# E-book_Reader_2.net
KiCad netlist of a schematic drawn in EAGLE
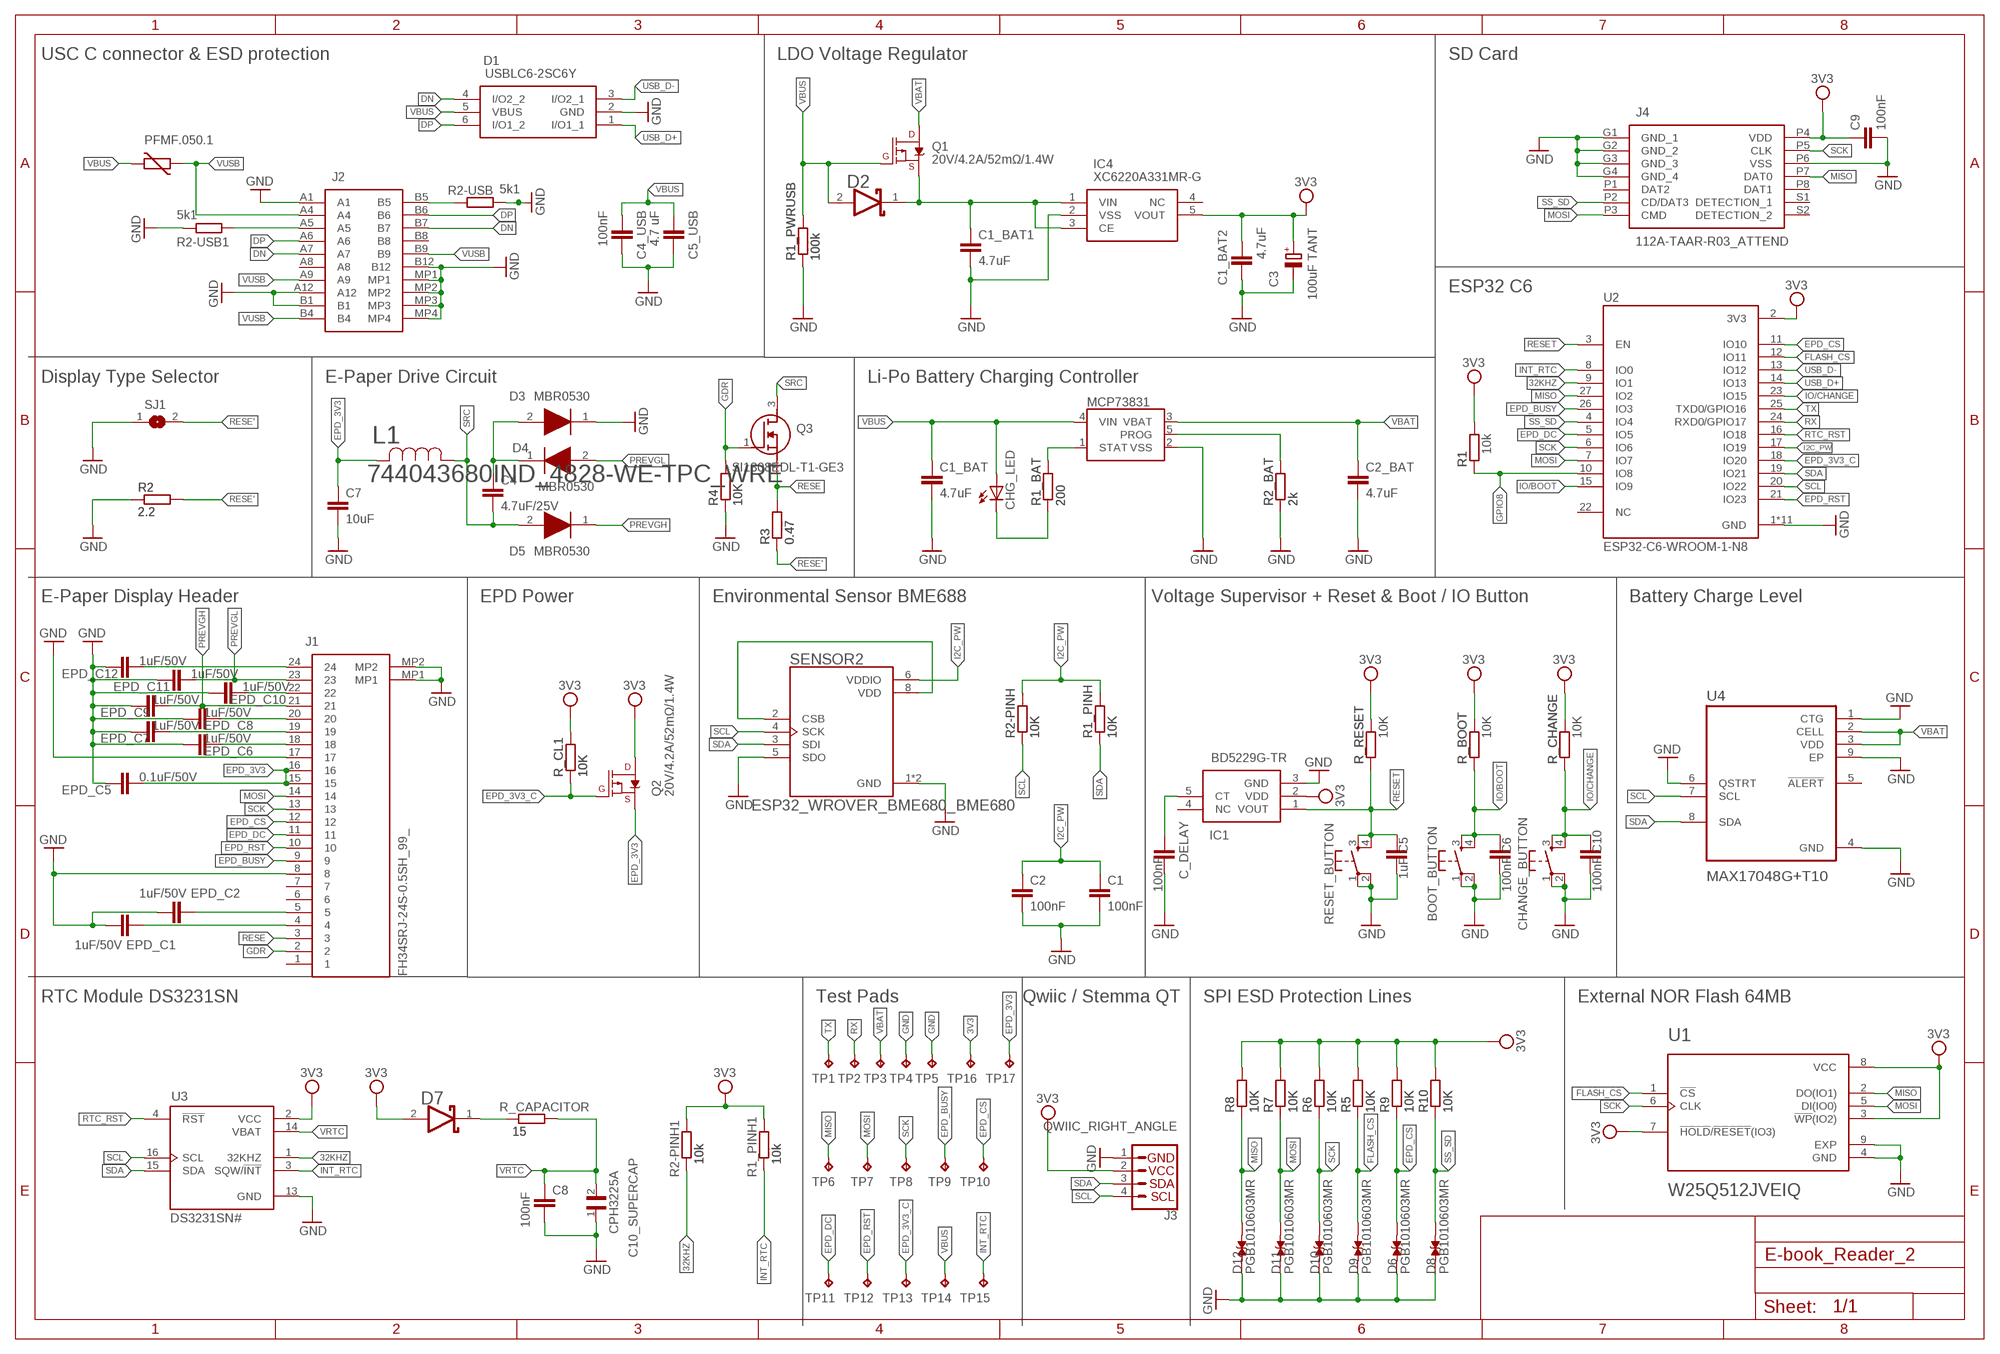
[diagram p0: schematic, sheet 1]

(export (version "E")
  (design (tool "Eeschema 10.0.6"))
  (components
    (comp (ref "BOOT_BUTTON")
      (value "BUTTON_CUSYOMV1")
      (footprint "eagle-import:MYBUTTON")
      (libsource (lib "eagle-import") (part "BUTTON_CUSYOMV1"))
    )
    (comp (ref "C1")
      (value "100nF")
      (footprint "eagle-import:EAGLE-LTSPICE_C0402")
      (libsource (lib "eagle-import") (part "EAGLE-LTSPICE_CC0402"))
    )
    (comp (ref "C1_BAT")
      (value "4.7uF")
      (footprint "eagle-import:EAGLE-LTSPICE_C0402")
      (libsource (lib "eagle-import") (part "EAGLE-LTSPICE_CC0402"))
    )
    (comp (ref "C1_BAT1")
      (value "4.7uF")
      (footprint "eagle-import:EAGLE-LTSPICE_C0402")
      (libsource (lib "eagle-import") (part "EAGLE-LTSPICE_CC0402"))
    )
    (comp (ref "C1_BAT2")
      (value "4.7uF")
      (footprint "eagle-import:EAGLE-LTSPICE_C0402")
      (libsource (lib "eagle-import") (part "EAGLE-LTSPICE_CC0402"))
    )
    (comp (ref "C2")
      (value "100nF")
      (footprint "eagle-import:EAGLE-LTSPICE_C0402")
      (libsource (lib "eagle-import") (part "EAGLE-LTSPICE_CC0402"))
    )
    (comp (ref "C2_BAT")
      (value "4.7uF")
      (footprint "eagle-import:EAGLE-LTSPICE_C0402")
      (libsource (lib "eagle-import") (part "EAGLE-LTSPICE_CC0402"))
    )
    (comp (ref "C3")
      (value "100uF TANT")
      (footprint "eagle-import:RCL_CT3528")
      (libsource (lib "eagle-import") (part "RCL_CPOL-EUCT3528"))
    )
    (comp (ref "C4")
      (value "4.7uF/25V")
      (footprint "eagle-import:EAGLE-LTSPICE_C0402")
      (libsource (lib "eagle-import") (part "EAGLE-LTSPICE_CC0402"))
    )
    (comp (ref "C4_USB")
      (value "100nF")
      (footprint "eagle-import:EAGLE-LTSPICE_C0402")
      (libsource (lib "eagle-import") (part "EAGLE-LTSPICE_CC0402"))
    )
    (comp (ref "C5")
      (value "1uF")
      (footprint "eagle-import:EAGLE-LTSPICE_C0402")
      (libsource (lib "eagle-import") (part "EAGLE-LTSPICE_CC0402"))
    )
    (comp (ref "C5_USB")
      (value "4.7 uF")
      (footprint "eagle-import:EAGLE-LTSPICE_C0402")
      (libsource (lib "eagle-import") (part "EAGLE-LTSPICE_CC0402"))
    )
    (comp (ref "C6")
      (value "100nF")
      (footprint "eagle-import:EAGLE-LTSPICE_C0402")
      (libsource (lib "eagle-import") (part "EAGLE-LTSPICE_CC0402"))
    )
    (comp (ref "C7")
      (value "10uF")
      (footprint "eagle-import:EAGLE-LTSPICE_C0402")
      (libsource (lib "eagle-import") (part "EAGLE-LTSPICE_CC0402"))
    )
    (comp (ref "C8")
      (value "100nF")
      (footprint "eagle-import:EAGLE-LTSPICE_C0402")
      (libsource (lib "eagle-import") (part "EAGLE-LTSPICE_CC0402"))
    )
    (comp (ref "C9")
      (value "100nF")
      (footprint "eagle-import:EAGLE-LTSPICE_C0402")
      (libsource (lib "eagle-import") (part "EAGLE-LTSPICE_CC0402"))
    )
    (comp (ref "C10")
      (value "100nF")
      (footprint "eagle-import:EAGLE-LTSPICE_C0402")
      (libsource (lib "eagle-import") (part "EAGLE-LTSPICE_CC0402"))
    )
    (comp (ref "C10_SUPERCAP")
      (value "CPH3225A")
      (footprint "eagle-import:CAPCP3225X100N")
      (fields (field (name "MF") "Seiko Instruments"))
      (libsource (lib "eagle-import") (part "CPH3225A"))
    )
    (comp (ref "CHANGE_BUTTON")
      (value "BUTTON_CUSYOMV1")
      (footprint "eagle-import:MYBUTTON")
      (libsource (lib "eagle-import") (part "BUTTON_CUSYOMV1"))
    )
    (comp (ref "CHG_LED")
      (value "ADAFRUIT_LEDCHIP-LED0603")
      (footprint "eagle-import:ADAFRUIT_CHIP-LED0603")
      (libsource (lib "eagle-import") (part "ADAFRUIT_LEDCHIP-LED0603"))
    )
    (comp (ref "C_DELAY")
      (value "100nF")
      (footprint "eagle-import:EAGLE-LTSPICE_C0402")
      (libsource (lib "eagle-import") (part "EAGLE-LTSPICE_CC0402"))
    )
    (comp (ref "D1")
      (value "USBLC6-2SC6Y")
      (footprint "eagle-import:SOT95P280X145-6N")
      (fields (field (name "MF") "STMicroelectronics"))
      (libsource (lib "eagle-import") (part "USBLC6-2SC6Y"))
    )
    (comp (ref "D2")
      (value "ESP32_WROVER_AVX---SD0805S020S1R0_AVX_SD0805S020S1R0_0_0AVX_SD0805S020S1R0_0_0")
      (footprint "eagle-import:ESP32_WROVER_AVX---SD0805S020S1R0_AVX_SD0805S020S1R0_0")
      (fields
        (field (name "DIGIKEY_PART_NUMBER") "478-7800-1-ND")
        (field (name "MF") "AVX")
        (field (name "MOUSER_PART_NUMBER") "581-SD0805S020S1R0")
      )
      (libsource (lib "eagle-import") (part "ESP32_WROVER_AVX---SD0805S020S1R0_AVX_SD0805S020S1R0_0_0AVX_SD0805S020S1R0_0_0"))
    )
    (comp (ref "D3")
      (value "MBR0530")
      (footprint "eagle-import:SOD3716X135N")
      (fields (field (name "MF") "ON Semiconductor"))
      (libsource (lib "eagle-import") (part "MBR0530"))
    )
    (comp (ref "D4")
      (value "MBR0530")
      (footprint "eagle-import:SOD3716X135N")
      (fields (field (name "MF") "ON Semiconductor"))
      (libsource (lib "eagle-import") (part "MBR0530"))
    )
    (comp (ref "D5")
      (value "MBR0530")
      (footprint "eagle-import:SOD3716X135N")
      (fields (field (name "MF") "ON Semiconductor"))
      (libsource (lib "eagle-import") (part "MBR0530"))
    )
    (comp (ref "D6")
      (value "PGB1010603MR")
      (footprint "eagle-import:DIOC1608X36N")
      (fields (field (name "MF") "Littelfuse Inc."))
      (libsource (lib "eagle-import") (part "PGB1010603MR"))
    )
    (comp (ref "D7")
      (value "ESP32_WROVER_AVX---SD0805S020S1R0_AVX_SD0805S020S1R0_0_0AVX_SD0805S020S1R0_0_0")
      (footprint "eagle-import:ESP32_WROVER_AVX---SD0805S020S1R0_AVX_SD0805S020S1R0_0")
      (fields
        (field (name "DIGIKEY_PART_NUMBER") "478-7800-1-ND")
        (field (name "MF") "AVX")
        (field (name "MOUSER_PART_NUMBER") "581-SD0805S020S1R0")
      )
      (libsource (lib "eagle-import") (part "ESP32_WROVER_AVX---SD0805S020S1R0_AVX_SD0805S020S1R0_0_0AVX_SD0805S020S1R0_0_0"))
    )
    (comp (ref "D8")
      (value "PGB1010603MR")
      (footprint "eagle-import:DIOC1608X36N")
      (fields (field (name "MF") "Littelfuse Inc."))
      (libsource (lib "eagle-import") (part "PGB1010603MR"))
    )
    (comp (ref "D9")
      (value "PGB1010603MR")
      (footprint "eagle-import:DIOC1608X36N")
      (fields (field (name "MF") "Littelfuse Inc."))
      (libsource (lib "eagle-import") (part "PGB1010603MR"))
    )
    (comp (ref "D10")
      (value "PGB1010603MR")
      (footprint "eagle-import:DIOC1608X36N")
      (fields (field (name "MF") "Littelfuse Inc."))
      (libsource (lib "eagle-import") (part "PGB1010603MR"))
    )
    (comp (ref "D11")
      (value "PGB1010603MR")
      (footprint "eagle-import:DIOC1608X36N")
      (fields (field (name "MF") "Littelfuse Inc."))
      (libsource (lib "eagle-import") (part "PGB1010603MR"))
    )
    (comp (ref "D12")
      (value "PGB1010603MR")
      (footprint "eagle-import:DIOC1608X36N")
      (fields (field (name "MF") "Littelfuse Inc."))
      (libsource (lib "eagle-import") (part "PGB1010603MR"))
    )
    (comp (ref "EPD_C1")
      (value "1uF/50V")
      (footprint "eagle-import:EAGLE-LTSPICE_C0402")
      (libsource (lib "eagle-import") (part "EAGLE-LTSPICE_CC0402"))
    )
    (comp (ref "EPD_C2")
      (value "1uF/50V")
      (footprint "eagle-import:EAGLE-LTSPICE_C0402")
      (libsource (lib "eagle-import") (part "EAGLE-LTSPICE_CC0402"))
    )
    (comp (ref "EPD_C5")
      (value "0.1uF/50V")
      (footprint "eagle-import:EAGLE-LTSPICE_C0402")
      (libsource (lib "eagle-import") (part "EAGLE-LTSPICE_CC0402"))
    )
    (comp (ref "EPD_C6")
      (value "1uF/50V")
      (footprint "eagle-import:EAGLE-LTSPICE_C0402")
      (libsource (lib "eagle-import") (part "EAGLE-LTSPICE_CC0402"))
    )
    (comp (ref "EPD_C7")
      (value "1uF/50V")
      (footprint "eagle-import:EAGLE-LTSPICE_C0402")
      (libsource (lib "eagle-import") (part "EAGLE-LTSPICE_CC0402"))
    )
    (comp (ref "EPD_C8")
      (value "1uF/50V")
      (footprint "eagle-import:EAGLE-LTSPICE_C0402")
      (libsource (lib "eagle-import") (part "EAGLE-LTSPICE_CC0402"))
    )
    (comp (ref "EPD_C9")
      (value "1uF/50V")
      (footprint "eagle-import:EAGLE-LTSPICE_C0402")
      (libsource (lib "eagle-import") (part "EAGLE-LTSPICE_CC0402"))
    )
    (comp (ref "EPD_C10")
      (value "1uF/50V")
      (footprint "eagle-import:EAGLE-LTSPICE_C0402")
      (libsource (lib "eagle-import") (part "EAGLE-LTSPICE_CC0402"))
    )
    (comp (ref "EPD_C11")
      (value "1uF/50V")
      (footprint "eagle-import:EAGLE-LTSPICE_C0402")
      (libsource (lib "eagle-import") (part "EAGLE-LTSPICE_CC0402"))
    )
    (comp (ref "EPD_C12")
      (value "1uF/50V")
      (footprint "eagle-import:EAGLE-LTSPICE_C0402")
      (libsource (lib "eagle-import") (part "EAGLE-LTSPICE_CC0402"))
    )
    (comp (ref "IC1")
      (value "BD5229G-TR")
      (footprint "eagle-import:SOT95P280X125-5N")
      (fields (field (name "MOUSER_PART_NUMBER") "755-BD5229G-TR"))
      (libsource (lib "eagle-import") (part "BD5229G-TR"))
    )
    (comp (ref "IC4")
      (value "XC6220A331MR-G")
      (footprint "eagle-import:SOT95P280X120-5N")
      (fields (field (name "MOUSER_PART_NUMBER") "865-XC6220A331MR-G"))
      (libsource (lib "eagle-import") (part "XC6220A331MR-G"))
    )
    (comp (ref "J1")
      (value "FH34SRJ-24S-0.5SH_99_")
      (footprint "eagle-import:FH34SRJ24S05SH99")
      (fields
        (field (name "MANUFACTURER_PART_NUMBER") "FH34SRJ-24S-0.5SH(99)")
        (field (name "MOUSER_PART_NUMBER") "798-FH34SRJ24S05SH99")
      )
      (libsource (lib "eagle-import") (part "FH34SRJ-24S-0.5SH_99_"))
    )
    (comp (ref "J2")
      (value "SAMACSYS_PARTS_USB4110-GF-A")
      (footprint "eagle-import:SAMACSYS_PARTS_USB4110GFA")
      (fields
        (field (name "MANUFACTURER_PART_NUMBER") "USB4110-GF-A")
        (field (name "MOUSER_PART_NUMBER") "640-USB4110-GF-A")
      )
      (libsource (lib "eagle-import") (part "SAMACSYS_PARTS_USB4110-GF-A"))
    )
    (comp (ref "J3")
      (value "QWIIC_RIGHT_ANGLE")
      (footprint "eagle-import:JST04_1MM_RA")
      (libsource (lib "eagle-import") (part "QWIIC_CONNECTORJS-1MM"))
    )
    (comp (ref "J4")
      (value "112A-TAAR-R03_ATTEND")
      (footprint "eagle-import:112ATAARR03ATTEND")
      (fields (field (name "MANUFACTURER_PART_NUMBER") "112A-TAAR-R03 ATTEND"))
      (libsource (lib "eagle-import") (part "112A-TAAR-R03_ATTEND"))
    )
    (comp (ref "L1")
      (value "744043680IND_4828-WE-TPC_WRE")
      (footprint "eagle-import:IND_4828-WE-TPC_WRE")
      (fields
        (field (name "MANUFACTURER_PART_NUMBER") "744043680")
        (field (name "COPYRIGHT") "Copyright (C) 2024 Ultra Librarian. All rights reserved.")
      )
      (libsource (lib "eagle-import") (part "744043680IND_4828-WE-TPC_WRE"))
    )
    (comp (ref "MCP73831")
      (value "ESP32_WROVER_SPARKFUN-IC-POWER_MCP73831")
      (footprint "eagle-import:ESP32_WROVER_SPARKFUN-IC-POWER_SOT23-5")
      (libsource (lib "eagle-import") (part "ESP32_WROVER_SPARKFUN-IC-POWER_MCP73831"))
    )
    (comp (ref "PFMF.050.1")
      (value "ESP32C6_VARISTORCN1812")
      (footprint "eagle-import:ESP32C6_VARISTOR_CT_CN1812")
      (libsource (lib "eagle-import") (part "ESP32C6_VARISTORCN1812"))
    )
    (comp (ref "Q1")
      (value "20V/4.2A/52mΩ/1.4W")
      (footprint "eagle-import:ESP32_WROVER_SPARKFUN-DISCRETESEMI_SOT23-3")
      (libsource (lib "eagle-import") (part "ESP32_WROVER_SPARKFUN-DISCRETESEMI_MOSFET_PCH-DMG2305UX-7"))
    )
    (comp (ref "Q2")
      (value "20V/4.2A/52mΩ/1.4W")
      (footprint "eagle-import:ESP32_WROVER_SPARKFUN-DISCRETESEMI_SOT23-3")
      (libsource (lib "eagle-import") (part "ESP32_WROVER_SPARKFUN-DISCRETESEMI_MOSFET_PCH-DMG2305UX-7"))
    )
    (comp (ref "Q3")
      (value "SI1308EDL-T1-GE3")
      (footprint "eagle-import:SOT65P210X110-3N")
      (fields (field (name "MF") "Vishay Siliconix"))
      (libsource (lib "eagle-import") (part "SI1308EDL-T1-GE3"))
    )
    (comp (ref "R1")
      (value "10k")
      (footprint "eagle-import:ESP32_WROVER_EAGLE-LTSPICE_R0402")
      (libsource (lib "eagle-import") (part "ESP32_WROVER_EAGLE-LTSPICE_RR0402"))
    )
    (comp (ref "R1_BAT")
      (value "200")
      (footprint "eagle-import:ESP32_WROVER_EAGLE-LTSPICE_R0402")
      (libsource (lib "eagle-import") (part "ESP32_WROVER_EAGLE-LTSPICE_RR0402"))
    )
    (comp (ref "R1_PINH")
      (value "10K")
      (footprint "eagle-import:ESP32_WROVER_EAGLE-LTSPICE_R0402")
      (libsource (lib "eagle-import") (part "ESP32_WROVER_EAGLE-LTSPICE_RR0402"))
    )
    (comp (ref "R1_PINH1")
      (value "10k")
      (footprint "eagle-import:ESP32_WROVER_EAGLE-LTSPICE_R0402")
      (libsource (lib "eagle-import") (part "ESP32_WROVER_EAGLE-LTSPICE_RR0402"))
    )
    (comp (ref "R1_PWRUSB")
      (value "100k")
      (footprint "eagle-import:ESP32_WROVER_EAGLE-LTSPICE_R0402")
      (libsource (lib "eagle-import") (part "ESP32_WROVER_EAGLE-LTSPICE_RR0402"))
    )
    (comp (ref "R2")
      (value "2.2")
      (footprint "eagle-import:ESP32_WROVER_EAGLE-LTSPICE_R0402")
      (libsource (lib "eagle-import") (part "ESP32_WROVER_EAGLE-LTSPICE_RR0402"))
    )
    (comp (ref "R2-PINH")
      (value "10K")
      (footprint "eagle-import:ESP32_WROVER_EAGLE-LTSPICE_R0402")
      (libsource (lib "eagle-import") (part "ESP32_WROVER_EAGLE-LTSPICE_RR0402"))
    )
    (comp (ref "R2-PINH1")
      (value "10k")
      (footprint "eagle-import:ESP32_WROVER_EAGLE-LTSPICE_R0402")
      (libsource (lib "eagle-import") (part "ESP32_WROVER_EAGLE-LTSPICE_RR0402"))
    )
    (comp (ref "R2-USB")
      (value "5k1")
      (footprint "eagle-import:ESP32_WROVER_EAGLE-LTSPICE_R0402")
      (libsource (lib "eagle-import") (part "ESP32_WROVER_EAGLE-LTSPICE_RR0402"))
    )
    (comp (ref "R2-USB1")
      (value "5k1")
      (footprint "eagle-import:ESP32_WROVER_EAGLE-LTSPICE_R0402")
      (libsource (lib "eagle-import") (part "ESP32_WROVER_EAGLE-LTSPICE_RR0402"))
    )
    (comp (ref "R2_BAT")
      (value "2k")
      (footprint "eagle-import:ESP32_WROVER_EAGLE-LTSPICE_R0402")
      (libsource (lib "eagle-import") (part "ESP32_WROVER_EAGLE-LTSPICE_RR0402"))
    )
    (comp (ref "R3")
      (value "0.47")
      (footprint "eagle-import:ESP32_WROVER_EAGLE-LTSPICE_R0402")
      (libsource (lib "eagle-import") (part "ESP32_WROVER_EAGLE-LTSPICE_RR0402"))
    )
    (comp (ref "R4")
      (value "10K")
      (footprint "eagle-import:ESP32_WROVER_EAGLE-LTSPICE_R0402")
      (libsource (lib "eagle-import") (part "ESP32_WROVER_EAGLE-LTSPICE_RR0402"))
    )
    (comp (ref "R5")
      (value "10K")
      (footprint "eagle-import:ESP32_WROVER_EAGLE-LTSPICE_R0402")
      (libsource (lib "eagle-import") (part "ESP32_WROVER_EAGLE-LTSPICE_RR0402"))
    )
    (comp (ref "R6")
      (value "10K")
      (footprint "eagle-import:ESP32_WROVER_EAGLE-LTSPICE_R0402")
      (libsource (lib "eagle-import") (part "ESP32_WROVER_EAGLE-LTSPICE_RR0402"))
    )
    (comp (ref "R7")
      (value "10K")
      (footprint "eagle-import:ESP32_WROVER_EAGLE-LTSPICE_R0402")
      (libsource (lib "eagle-import") (part "ESP32_WROVER_EAGLE-LTSPICE_RR0402"))
    )
    (comp (ref "R8")
      (value "10K")
      (footprint "eagle-import:ESP32_WROVER_EAGLE-LTSPICE_R0402")
      (libsource (lib "eagle-import") (part "ESP32_WROVER_EAGLE-LTSPICE_RR0402"))
    )
    (comp (ref "R9")
      (value "10K")
      (footprint "eagle-import:ESP32_WROVER_EAGLE-LTSPICE_R0402")
      (libsource (lib "eagle-import") (part "ESP32_WROVER_EAGLE-LTSPICE_RR0402"))
    )
    (comp (ref "R10")
      (value "10K")
      (footprint "eagle-import:ESP32_WROVER_EAGLE-LTSPICE_R0402")
      (libsource (lib "eagle-import") (part "ESP32_WROVER_EAGLE-LTSPICE_RR0402"))
    )
    (comp (ref "RESET_BUTTON")
      (value "BUTTON_CUSYOMV1")
      (footprint "eagle-import:MYBUTTON")
      (libsource (lib "eagle-import") (part "BUTTON_CUSYOMV1"))
    )
    (comp (ref "R_BOOT")
      (value "10K")
      (footprint "eagle-import:ESP32_WROVER_EAGLE-LTSPICE_R0402")
      (libsource (lib "eagle-import") (part "ESP32_WROVER_EAGLE-LTSPICE_RR0402"))
    )
    (comp (ref "R_CAPACITOR")
      (value "15")
      (footprint "eagle-import:ESP32_WROVER_EAGLE-LTSPICE_R0402")
      (libsource (lib "eagle-import") (part "ESP32_WROVER_EAGLE-LTSPICE_RR0402"))
    )
    (comp (ref "R_CHANGE")
      (value "10K")
      (footprint "eagle-import:ESP32_WROVER_EAGLE-LTSPICE_R0402")
      (libsource (lib "eagle-import") (part "ESP32_WROVER_EAGLE-LTSPICE_RR0402"))
    )
    (comp (ref "R_CL1")
      (value "10K")
      (footprint "eagle-import:ESP32_WROVER_EAGLE-LTSPICE_R0402")
      (libsource (lib "eagle-import") (part "ESP32_WROVER_EAGLE-LTSPICE_RR0402"))
    )
    (comp (ref "R_RESET")
      (value "10K")
      (footprint "eagle-import:ESP32_WROVER_EAGLE-LTSPICE_R0402")
      (libsource (lib "eagle-import") (part "ESP32_WROVER_EAGLE-LTSPICE_RR0402"))
    )
    (comp (ref "SENSOR2")
      (value "ESP32_WROVER_BME680_BME680")
      (footprint "eagle-import:ESP32_WROVER_BME680_PSON80P300X300X100-8N")
      (fields (field (name "MF") "Bosch Sensortec") (field (name "MP") "BME680"))
      (libsource (lib "eagle-import") (part "ESP32_WROVER_BME680_BME680"))
    )
    (comp (ref "SJ1") (value "SJ") (footprint "eagle-import:SJ") (libsource (lib "eagle-import") (part "SJ")))
    (comp (ref "TP1")
      (value "TPTP20R")
      (footprint "eagle-import:TP20R")
      (libsource (lib "eagle-import") (part "TPTP20R"))
    )
    (comp (ref "TP2")
      (value "TPTP20R")
      (footprint "eagle-import:TP20R")
      (libsource (lib "eagle-import") (part "TPTP20R"))
    )
    (comp (ref "TP3")
      (value "TPTP20R")
      (footprint "eagle-import:TP20R")
      (libsource (lib "eagle-import") (part "TPTP20R"))
    )
    (comp (ref "TP4")
      (value "TPTP20R")
      (footprint "eagle-import:TP20R")
      (libsource (lib "eagle-import") (part "TPTP20R"))
    )
    (comp (ref "TP5")
      (value "TPTP20R")
      (footprint "eagle-import:TP20R")
      (libsource (lib "eagle-import") (part "TPTP20R"))
    )
    (comp (ref "TP6")
      (value "TPTP20R")
      (footprint "eagle-import:TP20R")
      (libsource (lib "eagle-import") (part "TPTP20R"))
    )
    (comp (ref "TP7")
      (value "TPTP20R")
      (footprint "eagle-import:TP20R")
      (libsource (lib "eagle-import") (part "TPTP20R"))
    )
    (comp (ref "TP8")
      (value "TPTP20R")
      (footprint "eagle-import:TP20R")
      (libsource (lib "eagle-import") (part "TPTP20R"))
    )
    (comp (ref "TP9")
      (value "TPTP20R")
      (footprint "eagle-import:TP20R")
      (libsource (lib "eagle-import") (part "TPTP20R"))
    )
    (comp (ref "TP10")
      (value "TPTP20R")
      (footprint "eagle-import:TP20R")
      (libsource (lib "eagle-import") (part "TPTP20R"))
    )
    (comp (ref "TP11")
      (value "TPTP20R")
      (footprint "eagle-import:TP20R")
      (libsource (lib "eagle-import") (part "TPTP20R"))
    )
    (comp (ref "TP12")
      (value "TPTP20R")
      (footprint "eagle-import:TP20R")
      (libsource (lib "eagle-import") (part "TPTP20R"))
    )
    (comp (ref "TP13")
      (value "TPTP20R")
      (footprint "eagle-import:TP20R")
      (libsource (lib "eagle-import") (part "TPTP20R"))
    )
    (comp (ref "TP14")
      (value "TPTP20R")
      (footprint "eagle-import:TP20R")
      (libsource (lib "eagle-import") (part "TPTP20R"))
    )
    (comp (ref "TP15")
      (value "TPTP20R")
      (footprint "eagle-import:TP20R")
      (libsource (lib "eagle-import") (part "TPTP20R"))
    )
    (comp (ref "TP16")
      (value "TPTP20R")
      (footprint "eagle-import:TP20R")
      (libsource (lib "eagle-import") (part "TPTP20R"))
    )
    (comp (ref "TP17")
      (value "TPTP20R")
      (footprint "eagle-import:TP20R")
      (libsource (lib "eagle-import") (part "TPTP20R"))
    )
    (comp (ref "U1")
      (value "W25Q512JVEIQ")
      (footprint "eagle-import:SON127P600X800X80-9N")
      (fields (field (name "MF") "Winbond Electronics"))
      (libsource (lib "eagle-import") (part "W25Q512JVEIQ"))
    )
    (comp (ref "U2")
      (value "ESP32-C6-WROOM-1-N8")
      (footprint "eagle-import:XCVR_ESP32-C6-WROOM-1-N8")
      (fields (field (name "MF") "Espressif Systems"))
      (libsource (lib "eagle-import") (part "ESP32-C6-WROOM-1-N8"))
    )
    (comp (ref "U3")
      (value "DS3231SN#")
      (footprint "eagle-import:SOIC127P1032X265-16N")
      (fields (field (name "MF") "Analog Devices"))
      (libsource (lib "eagle-import") (part "DS3231SN#"))
    )
    (comp (ref "U4")
      (value "MAX17048G+T10")
      (footprint "eagle-import:SON50P200X200X80-9N")
      (fields (field (name "MF") "Analog Devices"))
      (libsource (lib "eagle-import") (part "MAX17048G+T10"))
    )
  )
  (nets
    (net (code "1") (name "3V3") (class "Default")
      (node (ref "C1_BAT2") (pin "1") (pinfunction "1_1") (pintype "passive"))
      (node (ref "C3") (pin "+") (pinfunction "+_+") (pintype "passive"))
      (node (ref "C9") (pin "1") (pinfunction "1_1") (pintype "passive"))
      (node (ref "D7") (pin "2") (pinfunction "ANODE_2") (pintype "bidirectional"))
      (node (ref "IC1") (pin "2") (pinfunction "VDD_2") (pintype "bidirectional"))
      (node (ref "IC4") (pin "5") (pinfunction "VOUT_5") (pintype "bidirectional"))
      (node (ref "J3") (pin "2") (pinfunction "2_2") (pintype "power_in"))
      (node (ref "J4") (pin "P4") (pinfunction "VDD_P4") (pintype "bidirectional"))
      (node (ref "Q2") (pin "3") (pinfunction "D_3") (pintype "bidirectional"))
      (node (ref "R1") (pin "2") (pinfunction "2_2") (pintype "passive"))
      (node (ref "R10") (pin "2") (pinfunction "2_2") (pintype "passive"))
      (node (ref "R1_PINH1") (pin "2") (pinfunction "2_2") (pintype "passive"))
      (node (ref "R2-PINH1") (pin "2") (pinfunction "2_2") (pintype "passive"))
      (node (ref "R5") (pin "2") (pinfunction "2_2") (pintype "passive"))
      (node (ref "R6") (pin "2") (pinfunction "2_2") (pintype "passive"))
      (node (ref "R7") (pin "2") (pinfunction "2_2") (pintype "passive"))
      (node (ref "R8") (pin "2") (pinfunction "2_2") (pintype "passive"))
      (node (ref "R9") (pin "2") (pinfunction "2_2") (pintype "passive"))
      (node (ref "R_BOOT") (pin "2") (pinfunction "2_2") (pintype "passive"))
      (node (ref "R_CHANGE") (pin "2") (pinfunction "2_2") (pintype "passive"))
      (node (ref "R_CL1") (pin "2") (pinfunction "2_2") (pintype "passive"))
      (node (ref "R_RESET") (pin "2") (pinfunction "2_2") (pintype "passive"))
      (node (ref "TP16") (pin "TP") (pinfunction "TP_TP") (pintype "input"))
      (node (ref "U1") (pin "3") (pinfunction "~{WP}(IO2)_3") (pintype "bidirectional"))
      (node (ref "U1") (pin "7") (pinfunction "~{HOLD}/~{RESET}(IO3)_7") (pintype "bidirectional"))
      (node (ref "U1") (pin "8") (pinfunction "VCC_8") (pintype "power_in"))
      (node (ref "U2") (pin "2") (pinfunction "3V3_2") (pintype "power_in"))
      (node (ref "U3") (pin "2") (pinfunction "VCC_2") (pintype "power_in"))
    )
    (net (code "2") (name "32KHZ") (class "Default")
      (node (ref "R2-PINH1") (pin "1") (pinfunction "1_1") (pintype "passive"))
      (node (ref "U2") (pin "9") (pinfunction "IO1_9") (pintype "bidirectional"))
      (node (ref "U3") (pin "1") (pinfunction "32KHZ_1") (pintype "output"))
    )
    (net (code "3") (name "DN") (class "Default")
      (node (ref "D1") (pin "4") (pinfunction "I/O2_2_4") (pintype "bidirectional"))
      (node (ref "J2") (pin "A7") (pinfunction "A7_A7") (pintype "bidirectional"))
      (node (ref "J2") (pin "B7") (pinfunction "B7_B7") (pintype "bidirectional"))
    )
    (net (code "4") (name "DP") (class "Default")
      (node (ref "D1") (pin "6") (pinfunction "I/O1_2_6") (pintype "bidirectional"))
      (node (ref "J2") (pin "A6") (pinfunction "A6_A6") (pintype "bidirectional"))
      (node (ref "J2") (pin "B6") (pinfunction "B6_B6") (pintype "bidirectional"))
    )
    (net (code "5") (name "EPD_3V3") (class "Default")
      (node (ref "C7") (pin "1") (pinfunction "1_1") (pintype "passive"))
      (node (ref "EPD_C5") (pin "1") (pinfunction "1_1") (pintype "passive"))
      (node (ref "J1") (pin "15") (pinfunction "15_15") (pintype "bidirectional"))
      (node (ref "J1") (pin "16") (pinfunction "16_16") (pintype "bidirectional"))
      (node (ref "L1") (pin "2") (pinfunction "2_2") (pintype "passive"))
      (node (ref "Q2") (pin "2") (pinfunction "S_2") (pintype "bidirectional"))
      (node (ref "TP17") (pin "TP") (pinfunction "TP_TP") (pintype "input"))
    )
    (net (code "6") (name "EPD_3V3_C") (class "Default")
      (node (ref "Q2") (pin "1") (pinfunction "G_1") (pintype "bidirectional"))
      (node (ref "R_CL1") (pin "1") (pinfunction "1_1") (pintype "passive"))
      (node (ref "TP13") (pin "TP") (pinfunction "TP_TP") (pintype "input"))
      (node (ref "U2") (pin "18") (pinfunction "IO20_18") (pintype "bidirectional"))
    )
    (net (code "7") (name "EPD_BUSY") (class "Default")
      (node (ref "J1") (pin "9") (pinfunction "9_9") (pintype "bidirectional"))
      (node (ref "TP9") (pin "TP") (pinfunction "TP_TP") (pintype "input"))
      (node (ref "U2") (pin "26") (pinfunction "IO3_26") (pintype "bidirectional"))
    )
    (net (code "8") (name "EPD_CS") (class "Default")
      (node (ref "D6") (pin "2") (pinfunction "2_2") (pintype "passive"))
      (node (ref "J1") (pin "12") (pinfunction "12_12") (pintype "bidirectional"))
      (node (ref "R9") (pin "1") (pinfunction "1_1") (pintype "passive"))
      (node (ref "TP10") (pin "TP") (pinfunction "TP_TP") (pintype "input"))
      (node (ref "U2") (pin "11") (pinfunction "IO10_11") (pintype "bidirectional"))
    )
    (net (code "9") (name "EPD_DC") (class "Default")
      (node (ref "J1") (pin "11") (pinfunction "11_11") (pintype "bidirectional"))
      (node (ref "TP11") (pin "TP") (pinfunction "TP_TP") (pintype "input"))
      (node (ref "U2") (pin "5") (pinfunction "IO5_5") (pintype "bidirectional"))
    )
    (net (code "10") (name "EPD_RST") (class "Default")
      (node (ref "J1") (pin "10") (pinfunction "10_10") (pintype "bidirectional"))
      (node (ref "TP12") (pin "TP") (pinfunction "TP_TP") (pintype "input"))
      (node (ref "U2") (pin "21") (pinfunction "IO23_21") (pintype "bidirectional"))
    )
    (net (code "11") (name "FLASH_CS") (class "Default")
      (node (ref "D9") (pin "2") (pinfunction "2_2") (pintype "passive"))
      (node (ref "R5") (pin "1") (pinfunction "1_1") (pintype "passive"))
      (node (ref "U1") (pin "1") (pinfunction "~{CS}_1") (pintype "input"))
      (node (ref "U2") (pin "12") (pinfunction "IO11_12") (pintype "bidirectional"))
    )
    (net (code "12") (name "GDR") (class "Default")
      (node (ref "J1") (pin "2") (pinfunction "2_2") (pintype "bidirectional"))
      (node (ref "Q3") (pin "1") (pinfunction "G_1") (pintype "bidirectional"))
      (node (ref "R4") (pin "2") (pinfunction "2_2") (pintype "passive"))
    )
    (net (code "13") (name "GND") (class "Default")
      (node (ref "BOOT_BUTTON") (pin "1") (pinfunction "1_1") (pintype "passive"))
      (node (ref "BOOT_BUTTON") (pin "2") (pinfunction "2_2") (pintype "passive"))
      (node (ref "C1") (pin "2") (pinfunction "2_2") (pintype "passive"))
      (node (ref "C10") (pin "2") (pinfunction "2_2") (pintype "passive"))
      (node (ref "C10_SUPERCAP") (pin "1") (pinfunction "1_1") (pintype "passive"))
      (node (ref "C1_BAT") (pin "2") (pinfunction "2_2") (pintype "passive"))
      (node (ref "C1_BAT1") (pin "2") (pinfunction "2_2") (pintype "passive"))
      (node (ref "C1_BAT2") (pin "2") (pinfunction "2_2") (pintype "passive"))
      (node (ref "C2") (pin "2") (pinfunction "2_2") (pintype "passive"))
      (node (ref "C2_BAT") (pin "2") (pinfunction "2_2") (pintype "passive"))
      (node (ref "C3") (pin "-") (pinfunction "-_-") (pintype "passive"))
      (node (ref "C4_USB") (pin "2") (pinfunction "2_2") (pintype "passive"))
      (node (ref "C5") (pin "2") (pinfunction "2_2") (pintype "passive"))
      (node (ref "C5_USB") (pin "2") (pinfunction "2_2") (pintype "passive"))
      (node (ref "C6") (pin "2") (pinfunction "2_2") (pintype "passive"))
      (node (ref "C7") (pin "2") (pinfunction "2_2") (pintype "passive"))
      (node (ref "C8") (pin "2") (pinfunction "2_2") (pintype "passive"))
      (node (ref "C9") (pin "2") (pinfunction "2_2") (pintype "passive"))
      (node (ref "CHANGE_BUTTON") (pin "1") (pinfunction "1_1") (pintype "passive"))
      (node (ref "CHANGE_BUTTON") (pin "2") (pinfunction "2_2") (pintype "passive"))
      (node (ref "C_DELAY") (pin "2") (pinfunction "2_2") (pintype "passive"))
      (node (ref "D1") (pin "2") (pinfunction "GND_2") (pintype "bidirectional"))
      (node (ref "D10") (pin "1") (pinfunction "1_1") (pintype "passive"))
      (node (ref "D11") (pin "1") (pinfunction "1_1") (pintype "passive"))
      (node (ref "D12") (pin "1") (pinfunction "1_1") (pintype "passive"))
      (node (ref "D3") (pin "1") (pinfunction "K_1") (pintype "bidirectional"))
      (node (ref "D6") (pin "1") (pinfunction "1_1") (pintype "passive"))
      (node (ref "D8") (pin "1") (pinfunction "1_1") (pintype "passive"))
      (node (ref "D9") (pin "1") (pinfunction "1_1") (pintype "passive"))
      (node (ref "EPD_C1") (pin "2") (pinfunction "2_2") (pintype "passive"))
      (node (ref "EPD_C10") (pin "2") (pinfunction "2_2") (pintype "passive"))
      (node (ref "EPD_C11") (pin "2") (pinfunction "2_2") (pintype "passive"))
      (node (ref "EPD_C12") (pin "2") (pinfunction "2_2") (pintype "passive"))
      (node (ref "EPD_C2") (pin "2") (pinfunction "2_2") (pintype "passive"))
      (node (ref "EPD_C5") (pin "2") (pinfunction "2_2") (pintype "passive"))
      (node (ref "EPD_C6") (pin "2") (pinfunction "2_2") (pintype "passive"))
      (node (ref "EPD_C7") (pin "2") (pinfunction "2_2") (pintype "passive"))
      (node (ref "EPD_C8") (pin "2") (pinfunction "2_2") (pintype "passive"))
      (node (ref "EPD_C9") (pin "2") (pinfunction "2_2") (pintype "passive"))
      (node (ref "IC1") (pin "3") (pinfunction "GND_3") (pintype "bidirectional"))
      (node (ref "IC4") (pin "2") (pinfunction "VSS_2") (pintype "bidirectional"))
      (node (ref "J1") (pin "17") (pinfunction "17_17") (pintype "bidirectional"))
      (node (ref "J1") (pin "8") (pinfunction "8_8") (pintype "bidirectional"))
      (node (ref "J1") (pin "MP1") (pinfunction "MP1_MP1") (pintype "bidirectional"))
      (node (ref "J1") (pin "MP2") (pinfunction "MP2_MP2") (pintype "bidirectional"))
      (node (ref "J2") (pin "A1") (pinfunction "A1_A1") (pintype "bidirectional"))
      (node (ref "J2") (pin "A12") (pinfunction "A12_A12") (pintype "bidirectional"))
      (node (ref "J2") (pin "B1") (pinfunction "B1_B1") (pintype "bidirectional"))
      (node (ref "J2") (pin "B12") (pinfunction "B12_B12") (pintype "bidirectional"))
      (node (ref "J2") (pin "MP1") (pinfunction "MP1_MP1") (pintype "bidirectional"))
      (node (ref "J2") (pin "MP2") (pinfunction "MP2_MP2") (pintype "bidirectional"))
      (node (ref "J2") (pin "MP3") (pinfunction "MP3_MP3") (pintype "bidirectional"))
      (node (ref "J2") (pin "MP4") (pinfunction "MP4_MP4") (pintype "bidirectional"))
      (node (ref "J3") (pin "1") (pinfunction "1_1") (pintype "power_in"))
      (node (ref "J4") (pin "G1") (pinfunction "GND_1_G1") (pintype "bidirectional"))
      (node (ref "J4") (pin "G2") (pinfunction "GND_2_G2") (pintype "bidirectional"))
      (node (ref "J4") (pin "G3") (pinfunction "GND_3_G3") (pintype "bidirectional"))
      (node (ref "J4") (pin "G4") (pinfunction "GND_4_G4") (pintype "bidirectional"))
      (node (ref "J4") (pin "P6") (pinfunction "VSS_P6") (pintype "bidirectional"))
      (node (ref "MCP73831") (pin "2") (pinfunction "VSS_2") (pintype "power_in"))
      (node (ref "R1_PWRUSB") (pin "1") (pinfunction "1_1") (pintype "passive"))
      (node (ref "R2") (pin "1") (pinfunction "1_1") (pintype "passive"))
      (node (ref "R2-USB") (pin "2") (pinfunction "2_2") (pintype "passive"))
      (node (ref "R2-USB1") (pin "1") (pinfunction "1_1") (pintype "passive"))
      (node (ref "R2_BAT") (pin "1") (pinfunction "1_1") (pintype "passive"))
      (node (ref "R4") (pin "1") (pinfunction "1_1") (pintype "passive"))
      (node (ref "RESET_BUTTON") (pin "1") (pinfunction "1_1") (pintype "passive"))
      (node (ref "RESET_BUTTON") (pin "2") (pinfunction "2_2") (pintype "passive"))
      (node (ref "SENSOR2") (pin "1") (pinfunction "GND_1") (pintype "power_in"))
      (node (ref "SENSOR2") (pin "5") (pinfunction "SDO_5") (pintype "bidirectional"))
      (node (ref "SENSOR2") (pin "7") (pinfunction "GND_7") (pintype "power_in"))
      (node (ref "SJ1") (pin "1") (pinfunction "1_1") (pintype "passive"))
      (node (ref "TP4") (pin "TP") (pinfunction "TP_TP") (pintype "input"))
      (node (ref "TP5") (pin "TP") (pinfunction "TP_TP") (pintype "input"))
      (node (ref "U1") (pin "4") (pinfunction "GND_4") (pintype "power_in"))
      (node (ref "U1") (pin "9") (pinfunction "EXP_9") (pintype "passive"))
      (node (ref "U2") (pin "1") (pinfunction "GND_1") (pintype "power_in"))
      (node (ref "U2") (pin "28") (pinfunction "GND_28") (pintype "power_in"))
      (node (ref "U2") (pin "29_1") (pinfunction "GND_29_1") (pintype "power_in"))
      (node (ref "U2") (pin "29_2") (pinfunction "GND_29_2") (pintype "power_in"))
      (node (ref "U2") (pin "29_3") (pinfunction "GND_29_3") (pintype "power_in"))
      (node (ref "U2") (pin "29_4") (pinfunction "GND_29_4") (pintype "power_in"))
      (node (ref "U2") (pin "29_5") (pinfunction "GND_29_5") (pintype "power_in"))
      (node (ref "U2") (pin "29_6") (pinfunction "GND_29_6") (pintype "power_in"))
      (node (ref "U2") (pin "29_7") (pinfunction "GND_29_7") (pintype "power_in"))
      (node (ref "U2") (pin "29_8") (pinfunction "GND_29_8") (pintype "power_in"))
      (node (ref "U2") (pin "29_9") (pinfunction "GND_29_9") (pintype "power_in"))
      (node (ref "U3") (pin "13") (pinfunction "GND_13") (pintype "power_in"))
      (node (ref "U4") (pin "1") (pinfunction "CTG_1") (pintype "power_in"))
      (node (ref "U4") (pin "4") (pinfunction "GND_4") (pintype "power_in"))
      (node (ref "U4") (pin "6") (pinfunction "QSTRT_6") (pintype "input"))
      (node (ref "U4") (pin "9") (pinfunction "EP_9") (pintype "power_in"))
    )
    (net (code "14") (name "GPIO8") (class "Default")
      (node (ref "R1") (pin "1") (pinfunction "1_1") (pintype "passive"))
      (node (ref "U2") (pin "10") (pinfunction "IO8_10") (pintype "bidirectional"))
    )
    (net (code "15") (name "I2C_PW") (class "Default")
      (node (ref "C1") (pin "1") (pinfunction "1_1") (pintype "passive"))
      (node (ref "C2") (pin "1") (pinfunction "1_1") (pintype "passive"))
      (node (ref "R1_PINH") (pin "2") (pinfunction "2_2") (pintype "passive"))
      (node (ref "R2-PINH") (pin "2") (pinfunction "2_2") (pintype "passive"))
      (node (ref "SENSOR2") (pin "6") (pinfunction "VDDIO_6") (pintype "power_in"))
      (node (ref "U2") (pin "17") (pinfunction "IO19_17") (pintype "bidirectional"))
    )
    (net (code "16") (name "INT_RTC") (class "Default")
      (node (ref "R1_PINH1") (pin "1") (pinfunction "1_1") (pintype "passive"))
      (node (ref "TP15") (pin "TP") (pinfunction "TP_TP") (pintype "input"))
      (node (ref "U2") (pin "8") (pinfunction "IO0_8") (pintype "bidirectional"))
      (node (ref "U3") (pin "3") (pinfunction "SQW/~{INT}_3") (pintype "output"))
    )
    (net (code "17") (name "IO{slash}BOOT") (class "Default")
      (node (ref "BOOT_BUTTON") (pin "3") (pinfunction "3_3") (pintype "passive"))
      (node (ref "BOOT_BUTTON") (pin "4") (pinfunction "4_4") (pintype "passive"))
      (node (ref "C6") (pin "1") (pinfunction "1_1") (pintype "passive"))
      (node (ref "R_BOOT") (pin "1") (pinfunction "1_1") (pintype "passive"))
      (node (ref "U2") (pin "15") (pinfunction "IO9_15") (pintype "bidirectional"))
    )
    (net (code "18") (name "IO{slash}CHANGE") (class "Default")
      (node (ref "C10") (pin "1") (pinfunction "1_1") (pintype "passive"))
      (node (ref "CHANGE_BUTTON") (pin "3") (pinfunction "3_3") (pintype "passive"))
      (node (ref "CHANGE_BUTTON") (pin "4") (pinfunction "4_4") (pintype "passive"))
      (node (ref "R_CHANGE") (pin "1") (pinfunction "1_1") (pintype "passive"))
      (node (ref "U2") (pin "23") (pinfunction "IO15_23") (pintype "bidirectional"))
    )
    (net (code "19") (name "MISO") (class "Default")
      (node (ref "D12") (pin "2") (pinfunction "2_2") (pintype "passive"))
      (node (ref "J4") (pin "P7") (pinfunction "DAT0_P7") (pintype "bidirectional"))
      (node (ref "R8") (pin "1") (pinfunction "1_1") (pintype "passive"))
      (node (ref "TP6") (pin "TP") (pinfunction "TP_TP") (pintype "input"))
      (node (ref "U1") (pin "2") (pinfunction "DO(IO1)_2") (pintype "bidirectional"))
      (node (ref "U2") (pin "27") (pinfunction "IO2_27") (pintype "bidirectional"))
    )
    (net (code "20") (name "MOSI") (class "Default")
      (node (ref "D11") (pin "2") (pinfunction "2_2") (pintype "passive"))
      (node (ref "J1") (pin "14") (pinfunction "14_14") (pintype "bidirectional"))
      (node (ref "J4") (pin "P3") (pinfunction "CMD_P3") (pintype "bidirectional"))
      (node (ref "R7") (pin "1") (pinfunction "1_1") (pintype "passive"))
      (node (ref "TP7") (pin "TP") (pinfunction "TP_TP") (pintype "input"))
      (node (ref "U1") (pin "5") (pinfunction "DI(IO0)_5") (pintype "bidirectional"))
      (node (ref "U2") (pin "7") (pinfunction "IO7_7") (pintype "bidirectional"))
    )
    (net (code "21") (name "Net-(CHG_LED-PadC)") (class "Default")
      (node (ref "CHG_LED") (pin "C") (pinfunction "C_C") (pintype "passive"))
      (node (ref "R1_BAT") (pin "1") (pinfunction "1_1") (pintype "passive"))
    )
    (net (code "22") (name "Net-(D2-CATHODE)") (class "Default")
      (node (ref "C1_BAT1") (pin "1") (pinfunction "1_1") (pintype "passive"))
      (node (ref "D2") (pin "1") (pinfunction "CATHODE_1") (pintype "bidirectional"))
      (node (ref "IC4") (pin "1") (pinfunction "VIN_1") (pintype "bidirectional"))
      (node (ref "IC4") (pin "3") (pinfunction "CE_3") (pintype "bidirectional"))
      (node (ref "Q1") (pin "2") (pinfunction "S_2") (pintype "bidirectional"))
    )
    (net (code "23") (name "Net-(D3-A)") (class "Default")
      (node (ref "C4") (pin "1") (pinfunction "1_1") (pintype "passive"))
      (node (ref "D3") (pin "2") (pinfunction "A_2") (pintype "bidirectional"))
      (node (ref "D4") (pin "1") (pinfunction "K_1") (pintype "bidirectional"))
    )
    (net (code "24") (name "Net-(D7-CATHODE)") (class "Default")
      (node (ref "D7") (pin "1") (pinfunction "CATHODE_1") (pintype "bidirectional"))
      (node (ref "R_CAPACITOR") (pin "1") (pinfunction "1_1") (pintype "passive"))
    )
    (net (code "25") (name "Net-(EPD_C1-Pad1)") (class "Default")
      (node (ref "EPD_C1") (pin "1") (pinfunction "1_1") (pintype "passive"))
      (node (ref "J1") (pin "4") (pinfunction "4_4") (pintype "bidirectional"))
    )
    (net (code "26") (name "Net-(EPD_C2-Pad1)") (class "Default")
      (node (ref "EPD_C2") (pin "1") (pinfunction "1_1") (pintype "passive"))
      (node (ref "J1") (pin "5") (pinfunction "5_5") (pintype "bidirectional"))
    )
    (net (code "27") (name "Net-(EPD_C6-Pad1)") (class "Default")
      (node (ref "EPD_C6") (pin "1") (pinfunction "1_1") (pintype "passive"))
      (node (ref "J1") (pin "18") (pinfunction "18_18") (pintype "bidirectional"))
    )
    (net (code "28") (name "Net-(EPD_C7-Pad1)") (class "Default")
      (node (ref "EPD_C7") (pin "1") (pinfunction "1_1") (pintype "passive"))
      (node (ref "J1") (pin "19") (pinfunction "19_19") (pintype "bidirectional"))
    )
    (net (code "29") (name "Net-(EPD_C8-Pad1)") (class "Default")
      (node (ref "EPD_C8") (pin "1") (pinfunction "1_1") (pintype "passive"))
      (node (ref "J1") (pin "20") (pinfunction "20_20") (pintype "bidirectional"))
    )
    (net (code "30") (name "Net-(EPD_C10-Pad1)") (class "Default")
      (node (ref "EPD_C10") (pin "1") (pinfunction "1_1") (pintype "passive"))
      (node (ref "J1") (pin "22") (pinfunction "22_22") (pintype "bidirectional"))
    )
    (net (code "31") (name "Net-(EPD_C12-Pad1)") (class "Default")
      (node (ref "EPD_C12") (pin "1") (pinfunction "1_1") (pintype "passive"))
      (node (ref "J1") (pin "24") (pinfunction "24_24") (pintype "bidirectional"))
    )
    (net (code "32") (name "Net-(IC1-CT)") (class "Default")
      (node (ref "C_DELAY") (pin "1") (pinfunction "1_1") (pintype "passive"))
      (node (ref "IC1") (pin "5") (pinfunction "CT_5") (pintype "bidirectional"))
    )
    (net (code "33") (name "Net-(J2-PadA5)") (class "Default")
      (node (ref "J2") (pin "A5") (pinfunction "A5_A5") (pintype "bidirectional"))
      (node (ref "R2-USB1") (pin "2") (pinfunction "2_2") (pintype "passive"))
    )
    (net (code "34") (name "Net-(J2-PadB5)") (class "Default")
      (node (ref "J2") (pin "B5") (pinfunction "B5_B5") (pintype "bidirectional"))
      (node (ref "R2-USB") (pin "1") (pinfunction "1_1") (pintype "passive"))
    )
    (net (code "35") (name "Net-(MCP73831-PROG)") (class "Default")
      (node (ref "MCP73831") (pin "5") (pinfunction "PROG_5") (pintype "input"))
      (node (ref "R2_BAT") (pin "2") (pinfunction "2_2") (pintype "passive"))
    )
    (net (code "36") (name "Net-(MCP73831-STAT)") (class "Default")
      (node (ref "MCP73831") (pin "1") (pinfunction "STAT_1") (pintype "output"))
      (node (ref "R1_BAT") (pin "2") (pinfunction "2_2") (pintype "passive"))
    )
    (net (code "37") (name "Net-(SENSOR2-CSB)") (class "Default")
      (node (ref "SENSOR2") (pin "2") (pinfunction "CSB_2") (pintype "input"))
      (node (ref "SENSOR2") (pin "8") (pinfunction "VDD_8") (pintype "power_in"))
    )
    (net (code "38") (name "PREVGH") (class "Default")
      (node (ref "D5") (pin "1") (pinfunction "K_1") (pintype "bidirectional"))
      (node (ref "EPD_C9") (pin "1") (pinfunction "1_1") (pintype "passive"))
      (node (ref "J1") (pin "21") (pinfunction "21_21") (pintype "bidirectional"))
    )
    (net (code "39") (name "PREVGL") (class "Default")
      (node (ref "D4") (pin "2") (pinfunction "A_2") (pintype "bidirectional"))
      (node (ref "EPD_C11") (pin "1") (pinfunction "1_1") (pintype "passive"))
      (node (ref "J1") (pin "23") (pinfunction "23_23") (pintype "bidirectional"))
    )
    (net (code "40") (name "RESE") (class "Default")
      (node (ref "J1") (pin "3") (pinfunction "3_3") (pintype "bidirectional"))
      (node (ref "Q3") (pin "2") (pinfunction "S_2") (pintype "bidirectional"))
      (node (ref "R3") (pin "2") (pinfunction "2_2") (pintype "passive"))
    )
    (net (code "41") (name "RESE'") (class "Default")
      (node (ref "R2") (pin "2") (pinfunction "2_2") (pintype "passive"))
      (node (ref "R3") (pin "1") (pinfunction "1_1") (pintype "passive"))
      (node (ref "SJ1") (pin "2") (pinfunction "2_2") (pintype "passive"))
    )
    (net (code "42") (name "RESET") (class "Default")
      (node (ref "C5") (pin "1") (pinfunction "1_1") (pintype "passive"))
      (node (ref "IC1") (pin "1") (pinfunction "VOUT_1") (pintype "bidirectional"))
      (node (ref "RESET_BUTTON") (pin "3") (pinfunction "3_3") (pintype "passive"))
      (node (ref "RESET_BUTTON") (pin "4") (pinfunction "4_4") (pintype "passive"))
      (node (ref "R_RESET") (pin "1") (pinfunction "1_1") (pintype "passive"))
      (node (ref "U2") (pin "3") (pinfunction "EN_3") (pintype "input"))
    )
    (net (code "43") (name "RTC_RST") (class "Default")
      (node (ref "U2") (pin "16") (pinfunction "IO18_16") (pintype "bidirectional"))
      (node (ref "U3") (pin "4") (pinfunction "~{RST}_4") (pintype "input"))
    )
    (net (code "44") (name "RX") (class "Default")
      (node (ref "TP2") (pin "TP") (pinfunction "TP_TP") (pintype "input"))
      (node (ref "U2") (pin "24") (pinfunction "RXD0/GPIO17_24") (pintype "bidirectional"))
    )
    (net (code "45") (name "SCK") (class "Default")
      (node (ref "D10") (pin "2") (pinfunction "2_2") (pintype "passive"))
      (node (ref "J1") (pin "13") (pinfunction "13_13") (pintype "bidirectional"))
      (node (ref "J4") (pin "P5") (pinfunction "CLK_P5") (pintype "bidirectional"))
      (node (ref "R6") (pin "1") (pinfunction "1_1") (pintype "passive"))
      (node (ref "TP8") (pin "TP") (pinfunction "TP_TP") (pintype "input"))
      (node (ref "U1") (pin "6") (pinfunction "CLK_6") (pintype "input"))
      (node (ref "U2") (pin "6") (pinfunction "IO6_6") (pintype "bidirectional"))
    )
    (net (code "46") (name "SCL") (class "Default")
      (node (ref "J3") (pin "4") (pinfunction "4_4") (pintype "passive"))
      (node (ref "R2-PINH") (pin "1") (pinfunction "1_1") (pintype "passive"))
      (node (ref "SENSOR2") (pin "4") (pinfunction "SCK_4") (pintype "input"))
      (node (ref "U2") (pin "20") (pinfunction "IO22_20") (pintype "bidirectional"))
      (node (ref "U3") (pin "16") (pinfunction "SCL_16") (pintype "input"))
      (node (ref "U4") (pin "7") (pinfunction "SCL_7") (pintype "input"))
    )
    (net (code "47") (name "SDA") (class "Default")
      (node (ref "J3") (pin "3") (pinfunction "3_3") (pintype "passive"))
      (node (ref "R1_PINH") (pin "1") (pinfunction "1_1") (pintype "passive"))
      (node (ref "SENSOR2") (pin "3") (pinfunction "SDI_3") (pintype "bidirectional"))
      (node (ref "U2") (pin "19") (pinfunction "IO21_19") (pintype "bidirectional"))
      (node (ref "U3") (pin "15") (pinfunction "SDA_15") (pintype "bidirectional"))
      (node (ref "U4") (pin "8") (pinfunction "SDA_8") (pintype "bidirectional"))
    )
    (net (code "48") (name "SRC") (class "Default")
      (node (ref "C4") (pin "2") (pinfunction "2_2") (pintype "passive"))
      (node (ref "D5") (pin "2") (pinfunction "A_2") (pintype "bidirectional"))
      (node (ref "L1") (pin "1") (pinfunction "1_1") (pintype "passive"))
      (node (ref "Q3") (pin "3") (pinfunction "D_3") (pintype "bidirectional"))
    )
    (net (code "49") (name "SS_SD") (class "Default")
      (node (ref "D8") (pin "2") (pinfunction "2_2") (pintype "passive"))
      (node (ref "J4") (pin "P2") (pinfunction "CD/DAT3_P2") (pintype "bidirectional"))
      (node (ref "R10") (pin "1") (pinfunction "1_1") (pintype "passive"))
      (node (ref "U2") (pin "4") (pinfunction "IO4_4") (pintype "bidirectional"))
    )
    (net (code "50") (name "TX") (class "Default")
      (node (ref "TP1") (pin "TP") (pinfunction "TP_TP") (pintype "input"))
      (node (ref "U2") (pin "25") (pinfunction "TXD0/GPIO16_25") (pintype "bidirectional"))
    )
    (net (code "51") (name "USB_D+") (class "Default")
      (node (ref "D1") (pin "1") (pinfunction "I/O1_1_1") (pintype "bidirectional"))
      (node (ref "U2") (pin "14") (pinfunction "IO13_14") (pintype "bidirectional"))
    )
    (net (code "52") (name "USB_D-") (class "Default")
      (node (ref "D1") (pin "3") (pinfunction "I/O2_1_3") (pintype "bidirectional"))
      (node (ref "U2") (pin "13") (pinfunction "IO12_13") (pintype "bidirectional"))
    )
    (net (code "53") (name "VBAT") (class "Default")
      (node (ref "C2_BAT") (pin "1") (pinfunction "1_1") (pintype "passive"))
      (node (ref "MCP73831") (pin "3") (pinfunction "VBAT_3") (pintype "power_in"))
      (node (ref "Q1") (pin "3") (pinfunction "D_3") (pintype "bidirectional"))
      (node (ref "TP3") (pin "TP") (pinfunction "TP_TP") (pintype "input"))
      (node (ref "U4") (pin "2") (pinfunction "CELL_2") (pintype "power_in"))
      (node (ref "U4") (pin "3") (pinfunction "VDD_3") (pintype "power_in"))
    )
    (net (code "54") (name "VBUS") (class "Default")
      (node (ref "C1_BAT") (pin "1") (pinfunction "1_1") (pintype "passive"))
      (node (ref "C4_USB") (pin "1") (pinfunction "1_1") (pintype "passive"))
      (node (ref "C5_USB") (pin "1") (pinfunction "1_1") (pintype "passive"))
      (node (ref "CHG_LED") (pin "A") (pinfunction "A_A") (pintype "passive"))
      (node (ref "D1") (pin "5") (pinfunction "VBUS_5") (pintype "bidirectional"))
      (node (ref "D2") (pin "2") (pinfunction "ANODE_2") (pintype "bidirectional"))
      (node (ref "MCP73831") (pin "4") (pinfunction "VIN_4") (pintype "power_in"))
      (node (ref "PFMF.050.1") (pin "2") (pinfunction "2_2") (pintype "passive"))
      (node (ref "Q1") (pin "1") (pinfunction "G_1") (pintype "bidirectional"))
      (node (ref "R1_PWRUSB") (pin "2") (pinfunction "2_2") (pintype "passive"))
      (node (ref "TP14") (pin "TP") (pinfunction "TP_TP") (pintype "input"))
    )
    (net (code "55") (name "VRTC") (class "Default")
      (node (ref "C10_SUPERCAP") (pin "2") (pinfunction "2_2") (pintype "passive"))
      (node (ref "C8") (pin "1") (pinfunction "1_1") (pintype "passive"))
      (node (ref "R_CAPACITOR") (pin "2") (pinfunction "2_2") (pintype "passive"))
      (node (ref "U3") (pin "14") (pinfunction "VBAT_14") (pintype "power_in"))
    )
    (net (code "56") (name "VUSB") (class "Default")
      (node (ref "J2") (pin "A4") (pinfunction "A4_A4") (pintype "bidirectional"))
      (node (ref "J2") (pin "A9") (pinfunction "A9_A9") (pintype "bidirectional"))
      (node (ref "J2") (pin "B4") (pinfunction "B4_B4") (pintype "bidirectional"))
      (node (ref "J2") (pin "B9") (pinfunction "B9_B9") (pintype "bidirectional"))
      (node (ref "PFMF.050.1") (pin "1") (pinfunction "1_1") (pintype "passive"))
    )
    (net (code "57") (name "unconnected-(IC1-NC-Pad4)") (class "Default")
      (node (ref "IC1") (pin "4") (pinfunction "NC_4") (pintype "no_connect"))
    )
    (net (code "58") (name "unconnected-(IC4-NC-Pad4)") (class "Default")
      (node (ref "IC4") (pin "4") (pinfunction "NC_4") (pintype "no_connect"))
    )
    (net (code "59") (name "unconnected-(J1-Pad1)") (class "Default")
      (node (ref "J1") (pin "1") (pinfunction "1_1") (pintype "bidirectional"))
    )
    (net (code "60") (name "unconnected-(J1-Pad6)") (class "Default")
      (node (ref "J1") (pin "6") (pinfunction "6_6") (pintype "bidirectional"))
    )
    (net (code "61") (name "unconnected-(J1-Pad7)") (class "Default")
      (node (ref "J1") (pin "7") (pinfunction "7_7") (pintype "bidirectional"))
    )
    (net (code "62") (name "unconnected-(J2-PadA8)") (class "Default")
      (node (ref "J2") (pin "A8") (pinfunction "A8_A8") (pintype "bidirectional"))
    )
    (net (code "63") (name "unconnected-(J2-PadB8)") (class "Default")
      (node (ref "J2") (pin "B8") (pinfunction "B8_B8") (pintype "bidirectional"))
    )
    (net (code "64") (name "unconnected-(J4-DAT1-PadP8)") (class "Default")
      (node (ref "J4") (pin "P8") (pinfunction "DAT1_P8") (pintype "bidirectional"))
    )
    (net (code "65") (name "unconnected-(J4-DAT2-PadP1)") (class "Default")
      (node (ref "J4") (pin "P1") (pinfunction "DAT2_P1") (pintype "bidirectional"))
    )
    (net (code "66") (name "unconnected-(J4-DETECTION_1-PadS1)") (class "Default")
      (node (ref "J4") (pin "S1") (pinfunction "DETECTION_1_S1") (pintype "bidirectional"))
    )
    (net (code "67") (name "unconnected-(J4-DETECTION_2-PadS2)") (class "Default")
      (node (ref "J4") (pin "S2") (pinfunction "DETECTION_2_S2") (pintype "bidirectional"))
    )
    (net (code "68") (name "unconnected-(U2-NC-Pad22)") (class "Default")
      (node (ref "U2") (pin "22") (pinfunction "NC_22") (pintype "no_connect"))
    )
    (net (code "69") (name "unconnected-(U4-~{ALERT}-Pad5)") (class "Default")
      (node (ref "U4") (pin "5") (pinfunction "~{ALERT}_5") (pintype "output"))
    )
  )
)
